# FLD_Logic.net
KiCad netlist of a schematic drawn in EAGLE
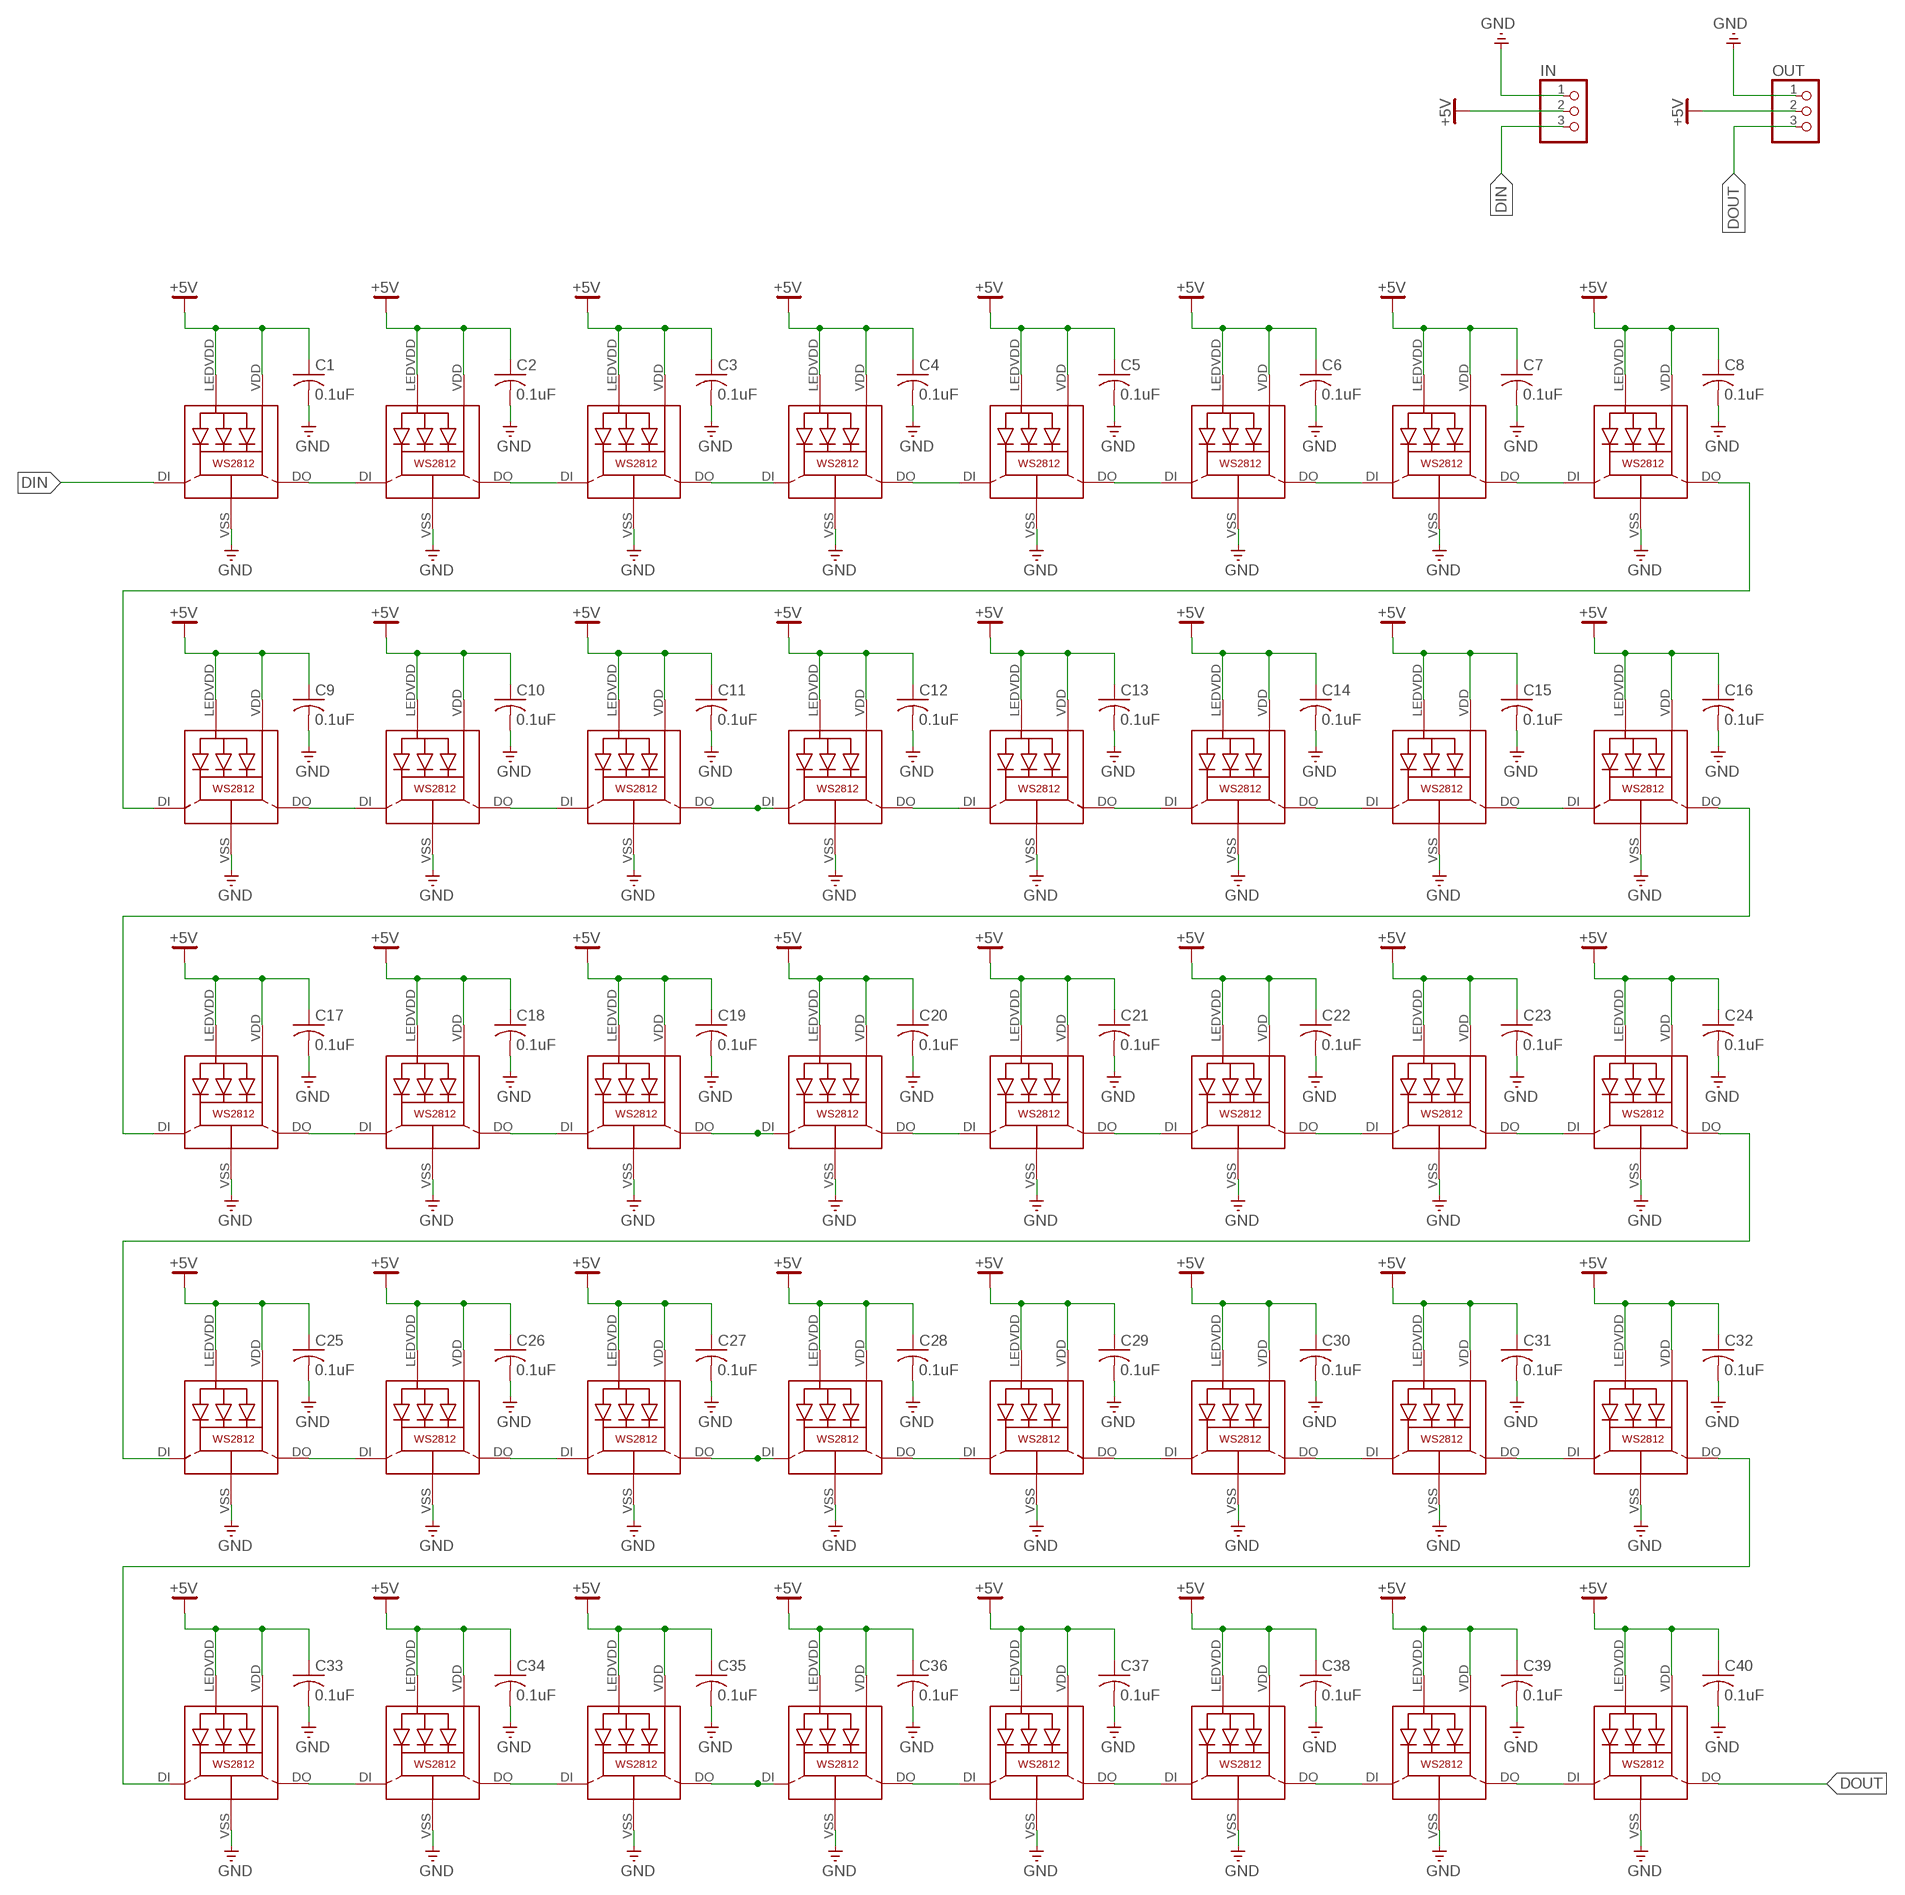
[diagram p0: schematic, sheet 1]

(export (version "E")
  (design (tool "Eeschema 10.0.6"))
  (components
    (comp (ref "C1")
      (value "0.1uF")
      (footprint "eagle-import:C0603")
      (libsource (lib "eagle-import") (part "C-USC0603"))
    )
    (comp (ref "C2")
      (value "0.1uF")
      (footprint "eagle-import:C0603")
      (libsource (lib "eagle-import") (part "C-USC0603"))
    )
    (comp (ref "C3")
      (value "0.1uF")
      (footprint "eagle-import:C0603")
      (libsource (lib "eagle-import") (part "C-USC0603"))
    )
    (comp (ref "C4")
      (value "0.1uF")
      (footprint "eagle-import:C0603")
      (libsource (lib "eagle-import") (part "C-USC0603"))
    )
    (comp (ref "C5")
      (value "0.1uF")
      (footprint "eagle-import:C0603")
      (libsource (lib "eagle-import") (part "C-USC0603"))
    )
    (comp (ref "C6")
      (value "0.1uF")
      (footprint "eagle-import:C0603")
      (libsource (lib "eagle-import") (part "C-USC0603"))
    )
    (comp (ref "C7")
      (value "0.1uF")
      (footprint "eagle-import:C0603")
      (libsource (lib "eagle-import") (part "C-USC0603"))
    )
    (comp (ref "C8")
      (value "0.1uF")
      (footprint "eagle-import:C0603")
      (libsource (lib "eagle-import") (part "C-USC0603"))
    )
    (comp (ref "C9")
      (value "0.1uF")
      (footprint "eagle-import:C0603")
      (libsource (lib "eagle-import") (part "C-USC0603"))
    )
    (comp (ref "C10")
      (value "0.1uF")
      (footprint "eagle-import:C0603")
      (libsource (lib "eagle-import") (part "C-USC0603"))
    )
    (comp (ref "C11")
      (value "0.1uF")
      (footprint "eagle-import:C0603")
      (libsource (lib "eagle-import") (part "C-USC0603"))
    )
    (comp (ref "C12")
      (value "0.1uF")
      (footprint "eagle-import:C0603")
      (libsource (lib "eagle-import") (part "C-USC0603"))
    )
    (comp (ref "C13")
      (value "0.1uF")
      (footprint "eagle-import:C0603")
      (libsource (lib "eagle-import") (part "C-USC0603"))
    )
    (comp (ref "C14")
      (value "0.1uF")
      (footprint "eagle-import:C0603")
      (libsource (lib "eagle-import") (part "C-USC0603"))
    )
    (comp (ref "C15")
      (value "0.1uF")
      (footprint "eagle-import:C0603")
      (libsource (lib "eagle-import") (part "C-USC0603"))
    )
    (comp (ref "C16")
      (value "0.1uF")
      (footprint "eagle-import:C0603")
      (libsource (lib "eagle-import") (part "C-USC0603"))
    )
    (comp (ref "C17")
      (value "0.1uF")
      (footprint "eagle-import:C0603")
      (libsource (lib "eagle-import") (part "C-USC0603"))
    )
    (comp (ref "C18")
      (value "0.1uF")
      (footprint "eagle-import:C0603")
      (libsource (lib "eagle-import") (part "C-USC0603"))
    )
    (comp (ref "C19")
      (value "0.1uF")
      (footprint "eagle-import:C0603")
      (libsource (lib "eagle-import") (part "C-USC0603"))
    )
    (comp (ref "C20")
      (value "0.1uF")
      (footprint "eagle-import:C0603")
      (libsource (lib "eagle-import") (part "C-USC0603"))
    )
    (comp (ref "C21")
      (value "0.1uF")
      (footprint "eagle-import:C0603")
      (libsource (lib "eagle-import") (part "C-USC0603"))
    )
    (comp (ref "C22")
      (value "0.1uF")
      (footprint "eagle-import:C0603")
      (libsource (lib "eagle-import") (part "C-USC0603"))
    )
    (comp (ref "C23")
      (value "0.1uF")
      (footprint "eagle-import:C0603")
      (libsource (lib "eagle-import") (part "C-USC0603"))
    )
    (comp (ref "C24")
      (value "0.1uF")
      (footprint "eagle-import:C0603")
      (libsource (lib "eagle-import") (part "C-USC0603"))
    )
    (comp (ref "C25")
      (value "0.1uF")
      (footprint "eagle-import:C0603")
      (libsource (lib "eagle-import") (part "C-USC0603"))
    )
    (comp (ref "C26")
      (value "0.1uF")
      (footprint "eagle-import:C0603")
      (libsource (lib "eagle-import") (part "C-USC0603"))
    )
    (comp (ref "C27")
      (value "0.1uF")
      (footprint "eagle-import:C0603")
      (libsource (lib "eagle-import") (part "C-USC0603"))
    )
    (comp (ref "C28")
      (value "0.1uF")
      (footprint "eagle-import:C0603")
      (libsource (lib "eagle-import") (part "C-USC0603"))
    )
    (comp (ref "C29")
      (value "0.1uF")
      (footprint "eagle-import:C0603")
      (libsource (lib "eagle-import") (part "C-USC0603"))
    )
    (comp (ref "C30")
      (value "0.1uF")
      (footprint "eagle-import:C0603")
      (libsource (lib "eagle-import") (part "C-USC0603"))
    )
    (comp (ref "C31")
      (value "0.1uF")
      (footprint "eagle-import:C0603")
      (libsource (lib "eagle-import") (part "C-USC0603"))
    )
    (comp (ref "C32")
      (value "0.1uF")
      (footprint "eagle-import:C0603")
      (libsource (lib "eagle-import") (part "C-USC0603"))
    )
    (comp (ref "C33")
      (value "0.1uF")
      (footprint "eagle-import:C0603")
      (libsource (lib "eagle-import") (part "C-USC0603"))
    )
    (comp (ref "C34")
      (value "0.1uF")
      (footprint "eagle-import:C0603")
      (libsource (lib "eagle-import") (part "C-USC0603"))
    )
    (comp (ref "C35")
      (value "0.1uF")
      (footprint "eagle-import:C0603")
      (libsource (lib "eagle-import") (part "C-USC0603"))
    )
    (comp (ref "C36")
      (value "0.1uF")
      (footprint "eagle-import:C0603")
      (libsource (lib "eagle-import") (part "C-USC0603"))
    )
    (comp (ref "C37")
      (value "0.1uF")
      (footprint "eagle-import:C0603")
      (libsource (lib "eagle-import") (part "C-USC0603"))
    )
    (comp (ref "C38")
      (value "0.1uF")
      (footprint "eagle-import:C0603")
      (libsource (lib "eagle-import") (part "C-USC0603"))
    )
    (comp (ref "C39")
      (value "0.1uF")
      (footprint "eagle-import:C0603")
      (libsource (lib "eagle-import") (part "C-USC0603"))
    )
    (comp (ref "C40")
      (value "0.1uF")
      (footprint "eagle-import:C0603")
      (libsource (lib "eagle-import") (part "C-USC0603"))
    )
    (comp (ref "IN")
      (value "PINHD-1X3")
      (footprint "eagle-import:1X03")
      (libsource (lib "eagle-import") (part "PINHD-1X3"))
    )
    (comp (ref "LED1")
      (value "WS2812")
      (footprint "eagle-import:WS2812")
      (libsource (lib "eagle-import") (part "WS2812"))
    )
    (comp (ref "LED2")
      (value "WS2812")
      (footprint "eagle-import:WS2812")
      (libsource (lib "eagle-import") (part "WS2812"))
    )
    (comp (ref "LED3")
      (value "WS2812")
      (footprint "eagle-import:WS2812")
      (libsource (lib "eagle-import") (part "WS2812"))
    )
    (comp (ref "LED4")
      (value "WS2812")
      (footprint "eagle-import:WS2812")
      (libsource (lib "eagle-import") (part "WS2812"))
    )
    (comp (ref "LED5")
      (value "WS2812")
      (footprint "eagle-import:WS2812")
      (libsource (lib "eagle-import") (part "WS2812"))
    )
    (comp (ref "LED6")
      (value "WS2812")
      (footprint "eagle-import:WS2812")
      (libsource (lib "eagle-import") (part "WS2812"))
    )
    (comp (ref "LED7")
      (value "WS2812")
      (footprint "eagle-import:WS2812")
      (libsource (lib "eagle-import") (part "WS2812"))
    )
    (comp (ref "LED8")
      (value "WS2812")
      (footprint "eagle-import:WS2812")
      (libsource (lib "eagle-import") (part "WS2812"))
    )
    (comp (ref "LED9")
      (value "WS2812")
      (footprint "eagle-import:WS2812")
      (libsource (lib "eagle-import") (part "WS2812"))
    )
    (comp (ref "LED10")
      (value "WS2812")
      (footprint "eagle-import:WS2812")
      (libsource (lib "eagle-import") (part "WS2812"))
    )
    (comp (ref "LED11")
      (value "WS2812")
      (footprint "eagle-import:WS2812")
      (libsource (lib "eagle-import") (part "WS2812"))
    )
    (comp (ref "LED12")
      (value "WS2812")
      (footprint "eagle-import:WS2812")
      (libsource (lib "eagle-import") (part "WS2812"))
    )
    (comp (ref "LED13")
      (value "WS2812")
      (footprint "eagle-import:WS2812")
      (libsource (lib "eagle-import") (part "WS2812"))
    )
    (comp (ref "LED14")
      (value "WS2812")
      (footprint "eagle-import:WS2812")
      (libsource (lib "eagle-import") (part "WS2812"))
    )
    (comp (ref "LED15")
      (value "WS2812")
      (footprint "eagle-import:WS2812")
      (libsource (lib "eagle-import") (part "WS2812"))
    )
    (comp (ref "LED16")
      (value "WS2812")
      (footprint "eagle-import:WS2812")
      (libsource (lib "eagle-import") (part "WS2812"))
    )
    (comp (ref "LED17")
      (value "WS2812")
      (footprint "eagle-import:WS2812")
      (libsource (lib "eagle-import") (part "WS2812"))
    )
    (comp (ref "LED18")
      (value "WS2812")
      (footprint "eagle-import:WS2812")
      (libsource (lib "eagle-import") (part "WS2812"))
    )
    (comp (ref "LED19")
      (value "WS2812")
      (footprint "eagle-import:WS2812")
      (libsource (lib "eagle-import") (part "WS2812"))
    )
    (comp (ref "LED20")
      (value "WS2812")
      (footprint "eagle-import:WS2812")
      (libsource (lib "eagle-import") (part "WS2812"))
    )
    (comp (ref "LED21")
      (value "WS2812")
      (footprint "eagle-import:WS2812")
      (libsource (lib "eagle-import") (part "WS2812"))
    )
    (comp (ref "LED22")
      (value "WS2812")
      (footprint "eagle-import:WS2812")
      (libsource (lib "eagle-import") (part "WS2812"))
    )
    (comp (ref "LED23")
      (value "WS2812")
      (footprint "eagle-import:WS2812")
      (libsource (lib "eagle-import") (part "WS2812"))
    )
    (comp (ref "LED24")
      (value "WS2812")
      (footprint "eagle-import:WS2812")
      (libsource (lib "eagle-import") (part "WS2812"))
    )
    (comp (ref "LED25")
      (value "WS2812")
      (footprint "eagle-import:WS2812")
      (libsource (lib "eagle-import") (part "WS2812"))
    )
    (comp (ref "LED26")
      (value "WS2812")
      (footprint "eagle-import:WS2812")
      (libsource (lib "eagle-import") (part "WS2812"))
    )
    (comp (ref "LED27")
      (value "WS2812")
      (footprint "eagle-import:WS2812")
      (libsource (lib "eagle-import") (part "WS2812"))
    )
    (comp (ref "LED28")
      (value "WS2812")
      (footprint "eagle-import:WS2812")
      (libsource (lib "eagle-import") (part "WS2812"))
    )
    (comp (ref "LED29")
      (value "WS2812")
      (footprint "eagle-import:WS2812")
      (libsource (lib "eagle-import") (part "WS2812"))
    )
    (comp (ref "LED30")
      (value "WS2812")
      (footprint "eagle-import:WS2812")
      (libsource (lib "eagle-import") (part "WS2812"))
    )
    (comp (ref "LED31")
      (value "WS2812")
      (footprint "eagle-import:WS2812")
      (libsource (lib "eagle-import") (part "WS2812"))
    )
    (comp (ref "LED32")
      (value "WS2812")
      (footprint "eagle-import:WS2812")
      (libsource (lib "eagle-import") (part "WS2812"))
    )
    (comp (ref "LED33")
      (value "WS2812")
      (footprint "eagle-import:WS2812")
      (libsource (lib "eagle-import") (part "WS2812"))
    )
    (comp (ref "LED34")
      (value "WS2812")
      (footprint "eagle-import:WS2812")
      (libsource (lib "eagle-import") (part "WS2812"))
    )
    (comp (ref "LED35")
      (value "WS2812")
      (footprint "eagle-import:WS2812")
      (libsource (lib "eagle-import") (part "WS2812"))
    )
    (comp (ref "LED36")
      (value "WS2812")
      (footprint "eagle-import:WS2812")
      (libsource (lib "eagle-import") (part "WS2812"))
    )
    (comp (ref "LED37")
      (value "WS2812")
      (footprint "eagle-import:WS2812")
      (libsource (lib "eagle-import") (part "WS2812"))
    )
    (comp (ref "LED38")
      (value "WS2812")
      (footprint "eagle-import:WS2812")
      (libsource (lib "eagle-import") (part "WS2812"))
    )
    (comp (ref "LED39")
      (value "WS2812")
      (footprint "eagle-import:WS2812")
      (libsource (lib "eagle-import") (part "WS2812"))
    )
    (comp (ref "LED40")
      (value "WS2812")
      (footprint "eagle-import:WS2812")
      (libsource (lib "eagle-import") (part "WS2812"))
    )
    (comp (ref "OUT")
      (value "PINHD-1X3")
      (footprint "eagle-import:1X03")
      (libsource (lib "eagle-import") (part "PINHD-1X3"))
    )
  )
  (nets
    (net (code "1") (name "+5V") (class "Default")
      (node (ref "C1") (pin "1") (pinfunction "1_1") (pintype "passive"))
      (node (ref "C10") (pin "1") (pinfunction "1_1") (pintype "passive"))
      (node (ref "C11") (pin "1") (pinfunction "1_1") (pintype "passive"))
      (node (ref "C12") (pin "1") (pinfunction "1_1") (pintype "passive"))
      (node (ref "C13") (pin "1") (pinfunction "1_1") (pintype "passive"))
      (node (ref "C14") (pin "1") (pinfunction "1_1") (pintype "passive"))
      (node (ref "C15") (pin "1") (pinfunction "1_1") (pintype "passive"))
      (node (ref "C16") (pin "1") (pinfunction "1_1") (pintype "passive"))
      (node (ref "C17") (pin "1") (pinfunction "1_1") (pintype "passive"))
      (node (ref "C18") (pin "1") (pinfunction "1_1") (pintype "passive"))
      (node (ref "C19") (pin "1") (pinfunction "1_1") (pintype "passive"))
      (node (ref "C2") (pin "1") (pinfunction "1_1") (pintype "passive"))
      (node (ref "C20") (pin "1") (pinfunction "1_1") (pintype "passive"))
      (node (ref "C21") (pin "1") (pinfunction "1_1") (pintype "passive"))
      (node (ref "C22") (pin "1") (pinfunction "1_1") (pintype "passive"))
      (node (ref "C23") (pin "1") (pinfunction "1_1") (pintype "passive"))
      (node (ref "C24") (pin "1") (pinfunction "1_1") (pintype "passive"))
      (node (ref "C25") (pin "1") (pinfunction "1_1") (pintype "passive"))
      (node (ref "C26") (pin "1") (pinfunction "1_1") (pintype "passive"))
      (node (ref "C27") (pin "1") (pinfunction "1_1") (pintype "passive"))
      (node (ref "C28") (pin "1") (pinfunction "1_1") (pintype "passive"))
      (node (ref "C29") (pin "1") (pinfunction "1_1") (pintype "passive"))
      (node (ref "C3") (pin "1") (pinfunction "1_1") (pintype "passive"))
      (node (ref "C30") (pin "1") (pinfunction "1_1") (pintype "passive"))
      (node (ref "C31") (pin "1") (pinfunction "1_1") (pintype "passive"))
      (node (ref "C32") (pin "1") (pinfunction "1_1") (pintype "passive"))
      (node (ref "C33") (pin "1") (pinfunction "1_1") (pintype "passive"))
      (node (ref "C34") (pin "1") (pinfunction "1_1") (pintype "passive"))
      (node (ref "C35") (pin "1") (pinfunction "1_1") (pintype "passive"))
      (node (ref "C36") (pin "1") (pinfunction "1_1") (pintype "passive"))
      (node (ref "C37") (pin "1") (pinfunction "1_1") (pintype "passive"))
      (node (ref "C38") (pin "1") (pinfunction "1_1") (pintype "passive"))
      (node (ref "C39") (pin "1") (pinfunction "1_1") (pintype "passive"))
      (node (ref "C4") (pin "1") (pinfunction "1_1") (pintype "passive"))
      (node (ref "C40") (pin "1") (pinfunction "1_1") (pintype "passive"))
      (node (ref "C5") (pin "1") (pinfunction "1_1") (pintype "passive"))
      (node (ref "C6") (pin "1") (pinfunction "1_1") (pintype "passive"))
      (node (ref "C7") (pin "1") (pinfunction "1_1") (pintype "passive"))
      (node (ref "C8") (pin "1") (pinfunction "1_1") (pintype "passive"))
      (node (ref "C9") (pin "1") (pinfunction "1_1") (pintype "passive"))
      (node (ref "IN") (pin "2") (pinfunction "2_2") (pintype "passive"))
      (node (ref "LED1") (pin "LEDVDD") (pinfunction "LEDVDD_LEDVDD") (pintype "power_in"))
      (node (ref "LED1") (pin "VDD") (pinfunction "VDD_VDD") (pintype "power_in"))
      (node (ref "LED10") (pin "LEDVDD") (pinfunction "LEDVDD_LEDVDD") (pintype "power_in"))
      (node (ref "LED10") (pin "VDD") (pinfunction "VDD_VDD") (pintype "power_in"))
      (node (ref "LED11") (pin "LEDVDD") (pinfunction "LEDVDD_LEDVDD") (pintype "power_in"))
      (node (ref "LED11") (pin "VDD") (pinfunction "VDD_VDD") (pintype "power_in"))
      (node (ref "LED12") (pin "LEDVDD") (pinfunction "LEDVDD_LEDVDD") (pintype "power_in"))
      (node (ref "LED12") (pin "VDD") (pinfunction "VDD_VDD") (pintype "power_in"))
      (node (ref "LED13") (pin "LEDVDD") (pinfunction "LEDVDD_LEDVDD") (pintype "power_in"))
      (node (ref "LED13") (pin "VDD") (pinfunction "VDD_VDD") (pintype "power_in"))
      (node (ref "LED14") (pin "LEDVDD") (pinfunction "LEDVDD_LEDVDD") (pintype "power_in"))
      (node (ref "LED14") (pin "VDD") (pinfunction "VDD_VDD") (pintype "power_in"))
      (node (ref "LED15") (pin "LEDVDD") (pinfunction "LEDVDD_LEDVDD") (pintype "power_in"))
      (node (ref "LED15") (pin "VDD") (pinfunction "VDD_VDD") (pintype "power_in"))
      (node (ref "LED16") (pin "LEDVDD") (pinfunction "LEDVDD_LEDVDD") (pintype "power_in"))
      (node (ref "LED16") (pin "VDD") (pinfunction "VDD_VDD") (pintype "power_in"))
      (node (ref "LED17") (pin "LEDVDD") (pinfunction "LEDVDD_LEDVDD") (pintype "power_in"))
      (node (ref "LED17") (pin "VDD") (pinfunction "VDD_VDD") (pintype "power_in"))
      (node (ref "LED18") (pin "LEDVDD") (pinfunction "LEDVDD_LEDVDD") (pintype "power_in"))
      (node (ref "LED18") (pin "VDD") (pinfunction "VDD_VDD") (pintype "power_in"))
      (node (ref "LED19") (pin "LEDVDD") (pinfunction "LEDVDD_LEDVDD") (pintype "power_in"))
      (node (ref "LED19") (pin "VDD") (pinfunction "VDD_VDD") (pintype "power_in"))
      (node (ref "LED2") (pin "LEDVDD") (pinfunction "LEDVDD_LEDVDD") (pintype "power_in"))
      (node (ref "LED2") (pin "VDD") (pinfunction "VDD_VDD") (pintype "power_in"))
      (node (ref "LED20") (pin "LEDVDD") (pinfunction "LEDVDD_LEDVDD") (pintype "power_in"))
      (node (ref "LED20") (pin "VDD") (pinfunction "VDD_VDD") (pintype "power_in"))
      (node (ref "LED21") (pin "LEDVDD") (pinfunction "LEDVDD_LEDVDD") (pintype "power_in"))
      (node (ref "LED21") (pin "VDD") (pinfunction "VDD_VDD") (pintype "power_in"))
      (node (ref "LED22") (pin "LEDVDD") (pinfunction "LEDVDD_LEDVDD") (pintype "power_in"))
      (node (ref "LED22") (pin "VDD") (pinfunction "VDD_VDD") (pintype "power_in"))
      (node (ref "LED23") (pin "LEDVDD") (pinfunction "LEDVDD_LEDVDD") (pintype "power_in"))
      (node (ref "LED23") (pin "VDD") (pinfunction "VDD_VDD") (pintype "power_in"))
      (node (ref "LED24") (pin "LEDVDD") (pinfunction "LEDVDD_LEDVDD") (pintype "power_in"))
      (node (ref "LED24") (pin "VDD") (pinfunction "VDD_VDD") (pintype "power_in"))
      (node (ref "LED25") (pin "LEDVDD") (pinfunction "LEDVDD_LEDVDD") (pintype "power_in"))
      (node (ref "LED25") (pin "VDD") (pinfunction "VDD_VDD") (pintype "power_in"))
      (node (ref "LED26") (pin "LEDVDD") (pinfunction "LEDVDD_LEDVDD") (pintype "power_in"))
      (node (ref "LED26") (pin "VDD") (pinfunction "VDD_VDD") (pintype "power_in"))
      (node (ref "LED27") (pin "LEDVDD") (pinfunction "LEDVDD_LEDVDD") (pintype "power_in"))
      (node (ref "LED27") (pin "VDD") (pinfunction "VDD_VDD") (pintype "power_in"))
      (node (ref "LED28") (pin "LEDVDD") (pinfunction "LEDVDD_LEDVDD") (pintype "power_in"))
      (node (ref "LED28") (pin "VDD") (pinfunction "VDD_VDD") (pintype "power_in"))
      (node (ref "LED29") (pin "LEDVDD") (pinfunction "LEDVDD_LEDVDD") (pintype "power_in"))
      (node (ref "LED29") (pin "VDD") (pinfunction "VDD_VDD") (pintype "power_in"))
      (node (ref "LED3") (pin "LEDVDD") (pinfunction "LEDVDD_LEDVDD") (pintype "power_in"))
      (node (ref "LED3") (pin "VDD") (pinfunction "VDD_VDD") (pintype "power_in"))
      (node (ref "LED30") (pin "LEDVDD") (pinfunction "LEDVDD_LEDVDD") (pintype "power_in"))
      (node (ref "LED30") (pin "VDD") (pinfunction "VDD_VDD") (pintype "power_in"))
      (node (ref "LED31") (pin "LEDVDD") (pinfunction "LEDVDD_LEDVDD") (pintype "power_in"))
      (node (ref "LED31") (pin "VDD") (pinfunction "VDD_VDD") (pintype "power_in"))
      (node (ref "LED32") (pin "LEDVDD") (pinfunction "LEDVDD_LEDVDD") (pintype "power_in"))
      (node (ref "LED32") (pin "VDD") (pinfunction "VDD_VDD") (pintype "power_in"))
      (node (ref "LED33") (pin "LEDVDD") (pinfunction "LEDVDD_LEDVDD") (pintype "power_in"))
      (node (ref "LED33") (pin "VDD") (pinfunction "VDD_VDD") (pintype "power_in"))
      (node (ref "LED34") (pin "LEDVDD") (pinfunction "LEDVDD_LEDVDD") (pintype "power_in"))
      (node (ref "LED34") (pin "VDD") (pinfunction "VDD_VDD") (pintype "power_in"))
      (node (ref "LED35") (pin "LEDVDD") (pinfunction "LEDVDD_LEDVDD") (pintype "power_in"))
      (node (ref "LED35") (pin "VDD") (pinfunction "VDD_VDD") (pintype "power_in"))
      (node (ref "LED36") (pin "LEDVDD") (pinfunction "LEDVDD_LEDVDD") (pintype "power_in"))
      (node (ref "LED36") (pin "VDD") (pinfunction "VDD_VDD") (pintype "power_in"))
      (node (ref "LED37") (pin "LEDVDD") (pinfunction "LEDVDD_LEDVDD") (pintype "power_in"))
      (node (ref "LED37") (pin "VDD") (pinfunction "VDD_VDD") (pintype "power_in"))
      (node (ref "LED38") (pin "LEDVDD") (pinfunction "LEDVDD_LEDVDD") (pintype "power_in"))
      (node (ref "LED38") (pin "VDD") (pinfunction "VDD_VDD") (pintype "power_in"))
      (node (ref "LED39") (pin "LEDVDD") (pinfunction "LEDVDD_LEDVDD") (pintype "power_in"))
      (node (ref "LED39") (pin "VDD") (pinfunction "VDD_VDD") (pintype "power_in"))
      (node (ref "LED4") (pin "LEDVDD") (pinfunction "LEDVDD_LEDVDD") (pintype "power_in"))
      (node (ref "LED4") (pin "VDD") (pinfunction "VDD_VDD") (pintype "power_in"))
      (node (ref "LED40") (pin "LEDVDD") (pinfunction "LEDVDD_LEDVDD") (pintype "power_in"))
      (node (ref "LED40") (pin "VDD") (pinfunction "VDD_VDD") (pintype "power_in"))
      (node (ref "LED5") (pin "LEDVDD") (pinfunction "LEDVDD_LEDVDD") (pintype "power_in"))
      (node (ref "LED5") (pin "VDD") (pinfunction "VDD_VDD") (pintype "power_in"))
      (node (ref "LED6") (pin "LEDVDD") (pinfunction "LEDVDD_LEDVDD") (pintype "power_in"))
      (node (ref "LED6") (pin "VDD") (pinfunction "VDD_VDD") (pintype "power_in"))
      (node (ref "LED7") (pin "LEDVDD") (pinfunction "LEDVDD_LEDVDD") (pintype "power_in"))
      (node (ref "LED7") (pin "VDD") (pinfunction "VDD_VDD") (pintype "power_in"))
      (node (ref "LED8") (pin "LEDVDD") (pinfunction "LEDVDD_LEDVDD") (pintype "power_in"))
      (node (ref "LED8") (pin "VDD") (pinfunction "VDD_VDD") (pintype "power_in"))
      (node (ref "LED9") (pin "LEDVDD") (pinfunction "LEDVDD_LEDVDD") (pintype "power_in"))
      (node (ref "LED9") (pin "VDD") (pinfunction "VDD_VDD") (pintype "power_in"))
      (node (ref "OUT") (pin "2") (pinfunction "2_2") (pintype "passive"))
    )
    (net (code "2") (name "DIN") (class "Default")
      (node (ref "IN") (pin "3") (pinfunction "3_3") (pintype "passive"))
      (node (ref "LED1") (pin "DI") (pinfunction "DI_DI") (pintype "input"))
    )
    (net (code "3") (name "DOUT") (class "Default")
      (node (ref "LED40") (pin "DO") (pinfunction "DO_DO") (pintype "output"))
      (node (ref "OUT") (pin "3") (pinfunction "3_3") (pintype "passive"))
    )
    (net (code "4") (name "GND") (class "Default")
      (node (ref "C1") (pin "2") (pinfunction "2_2") (pintype "passive"))
      (node (ref "C10") (pin "2") (pinfunction "2_2") (pintype "passive"))
      (node (ref "C11") (pin "2") (pinfunction "2_2") (pintype "passive"))
      (node (ref "C12") (pin "2") (pinfunction "2_2") (pintype "passive"))
      (node (ref "C13") (pin "2") (pinfunction "2_2") (pintype "passive"))
      (node (ref "C14") (pin "2") (pinfunction "2_2") (pintype "passive"))
      (node (ref "C15") (pin "2") (pinfunction "2_2") (pintype "passive"))
      (node (ref "C16") (pin "2") (pinfunction "2_2") (pintype "passive"))
      (node (ref "C17") (pin "2") (pinfunction "2_2") (pintype "passive"))
      (node (ref "C18") (pin "2") (pinfunction "2_2") (pintype "passive"))
      (node (ref "C19") (pin "2") (pinfunction "2_2") (pintype "passive"))
      (node (ref "C2") (pin "2") (pinfunction "2_2") (pintype "passive"))
      (node (ref "C20") (pin "2") (pinfunction "2_2") (pintype "passive"))
      (node (ref "C21") (pin "2") (pinfunction "2_2") (pintype "passive"))
      (node (ref "C22") (pin "2") (pinfunction "2_2") (pintype "passive"))
      (node (ref "C23") (pin "2") (pinfunction "2_2") (pintype "passive"))
      (node (ref "C24") (pin "2") (pinfunction "2_2") (pintype "passive"))
      (node (ref "C25") (pin "2") (pinfunction "2_2") (pintype "passive"))
      (node (ref "C26") (pin "2") (pinfunction "2_2") (pintype "passive"))
      (node (ref "C27") (pin "2") (pinfunction "2_2") (pintype "passive"))
      (node (ref "C28") (pin "2") (pinfunction "2_2") (pintype "passive"))
      (node (ref "C29") (pin "2") (pinfunction "2_2") (pintype "passive"))
      (node (ref "C3") (pin "2") (pinfunction "2_2") (pintype "passive"))
      (node (ref "C30") (pin "2") (pinfunction "2_2") (pintype "passive"))
      (node (ref "C31") (pin "2") (pinfunction "2_2") (pintype "passive"))
      (node (ref "C32") (pin "2") (pinfunction "2_2") (pintype "passive"))
      (node (ref "C33") (pin "2") (pinfunction "2_2") (pintype "passive"))
      (node (ref "C34") (pin "2") (pinfunction "2_2") (pintype "passive"))
      (node (ref "C35") (pin "2") (pinfunction "2_2") (pintype "passive"))
      (node (ref "C36") (pin "2") (pinfunction "2_2") (pintype "passive"))
      (node (ref "C37") (pin "2") (pinfunction "2_2") (pintype "passive"))
      (node (ref "C38") (pin "2") (pinfunction "2_2") (pintype "passive"))
      (node (ref "C39") (pin "2") (pinfunction "2_2") (pintype "passive"))
      (node (ref "C4") (pin "2") (pinfunction "2_2") (pintype "passive"))
      (node (ref "C40") (pin "2") (pinfunction "2_2") (pintype "passive"))
      (node (ref "C5") (pin "2") (pinfunction "2_2") (pintype "passive"))
      (node (ref "C6") (pin "2") (pinfunction "2_2") (pintype "passive"))
      (node (ref "C7") (pin "2") (pinfunction "2_2") (pintype "passive"))
      (node (ref "C8") (pin "2") (pinfunction "2_2") (pintype "passive"))
      (node (ref "C9") (pin "2") (pinfunction "2_2") (pintype "passive"))
      (node (ref "IN") (pin "1") (pinfunction "1_1") (pintype "passive"))
      (node (ref "LED1") (pin "VSS") (pinfunction "GND_VSS") (pintype "power_in"))
      (node (ref "LED10") (pin "VSS") (pinfunction "GND_VSS") (pintype "power_in"))
      (node (ref "LED11") (pin "VSS") (pinfunction "GND_VSS") (pintype "power_in"))
      (node (ref "LED12") (pin "VSS") (pinfunction "GND_VSS") (pintype "power_in"))
      (node (ref "LED13") (pin "VSS") (pinfunction "GND_VSS") (pintype "power_in"))
      (node (ref "LED14") (pin "VSS") (pinfunction "GND_VSS") (pintype "power_in"))
      (node (ref "LED15") (pin "VSS") (pinfunction "GND_VSS") (pintype "power_in"))
      (node (ref "LED16") (pin "VSS") (pinfunction "GND_VSS") (pintype "power_in"))
      (node (ref "LED17") (pin "VSS") (pinfunction "GND_VSS") (pintype "power_in"))
      (node (ref "LED18") (pin "VSS") (pinfunction "GND_VSS") (pintype "power_in"))
      (node (ref "LED19") (pin "VSS") (pinfunction "GND_VSS") (pintype "power_in"))
      (node (ref "LED2") (pin "VSS") (pinfunction "GND_VSS") (pintype "power_in"))
      (node (ref "LED20") (pin "VSS") (pinfunction "GND_VSS") (pintype "power_in"))
      (node (ref "LED21") (pin "VSS") (pinfunction "GND_VSS") (pintype "power_in"))
      (node (ref "LED22") (pin "VSS") (pinfunction "GND_VSS") (pintype "power_in"))
      (node (ref "LED23") (pin "VSS") (pinfunction "GND_VSS") (pintype "power_in"))
      (node (ref "LED24") (pin "VSS") (pinfunction "GND_VSS") (pintype "power_in"))
      (node (ref "LED25") (pin "VSS") (pinfunction "GND_VSS") (pintype "power_in"))
      (node (ref "LED26") (pin "VSS") (pinfunction "GND_VSS") (pintype "power_in"))
      (node (ref "LED27") (pin "VSS") (pinfunction "GND_VSS") (pintype "power_in"))
      (node (ref "LED28") (pin "VSS") (pinfunction "GND_VSS") (pintype "power_in"))
      (node (ref "LED29") (pin "VSS") (pinfunction "GND_VSS") (pintype "power_in"))
      (node (ref "LED3") (pin "VSS") (pinfunction "GND_VSS") (pintype "power_in"))
      (node (ref "LED30") (pin "VSS") (pinfunction "GND_VSS") (pintype "power_in"))
      (node (ref "LED31") (pin "VSS") (pinfunction "GND_VSS") (pintype "power_in"))
      (node (ref "LED32") (pin "VSS") (pinfunction "GND_VSS") (pintype "power_in"))
      (node (ref "LED33") (pin "VSS") (pinfunction "GND_VSS") (pintype "power_in"))
      (node (ref "LED34") (pin "VSS") (pinfunction "GND_VSS") (pintype "power_in"))
      (node (ref "LED35") (pin "VSS") (pinfunction "GND_VSS") (pintype "power_in"))
      (node (ref "LED36") (pin "VSS") (pinfunction "GND_VSS") (pintype "power_in"))
      (node (ref "LED37") (pin "VSS") (pinfunction "GND_VSS") (pintype "power_in"))
      (node (ref "LED38") (pin "VSS") (pinfunction "GND_VSS") (pintype "power_in"))
      (node (ref "LED39") (pin "VSS") (pinfunction "GND_VSS") (pintype "power_in"))
      (node (ref "LED4") (pin "VSS") (pinfunction "GND_VSS") (pintype "power_in"))
      (node (ref "LED40") (pin "VSS") (pinfunction "GND_VSS") (pintype "power_in"))
      (node (ref "LED5") (pin "VSS") (pinfunction "GND_VSS") (pintype "power_in"))
      (node (ref "LED6") (pin "VSS") (pinfunction "GND_VSS") (pintype "power_in"))
      (node (ref "LED7") (pin "VSS") (pinfunction "GND_VSS") (pintype "power_in"))
      (node (ref "LED8") (pin "VSS") (pinfunction "GND_VSS") (pintype "power_in"))
      (node (ref "LED9") (pin "VSS") (pinfunction "GND_VSS") (pintype "power_in"))
      (node (ref "OUT") (pin "1") (pinfunction "1_1") (pintype "passive"))
    )
    (net (code "5") (name "Net-(LED1-PadDO)") (class "Default")
      (node (ref "LED1") (pin "DO") (pinfunction "DO_DO") (pintype "output"))
      (node (ref "LED2") (pin "DI") (pinfunction "DI_DI") (pintype "input"))
    )
    (net (code "6") (name "Net-(LED2-PadDO)") (class "Default")
      (node (ref "LED2") (pin "DO") (pinfunction "DO_DO") (pintype "output"))
      (node (ref "LED3") (pin "DI") (pinfunction "DI_DI") (pintype "input"))
    )
    (net (code "7") (name "Net-(LED4-PadDO)") (class "Default")
      (node (ref "LED4") (pin "DO") (pinfunction "DO_DO") (pintype "output"))
      (node (ref "LED5") (pin "DI") (pinfunction "DI_DI") (pintype "input"))
    )
    (net (code "8") (name "Net-(LED5-PadDO)") (class "Default")
      (node (ref "LED5") (pin "DO") (pinfunction "DO_DO") (pintype "output"))
      (node (ref "LED6") (pin "DI") (pinfunction "DI_DI") (pintype "input"))
    )
    (net (code "9") (name "Net-(LED6-PadDO)") (class "Default")
      (node (ref "LED6") (pin "DO") (pinfunction "DO_DO") (pintype "output"))
      (node (ref "LED7") (pin "DI") (pinfunction "DI_DI") (pintype "input"))
    )
    (net (code "10") (name "Net-(LED7-PadDO)") (class "Default")
      (node (ref "LED7") (pin "DO") (pinfunction "DO_DO") (pintype "output"))
      (node (ref "LED8") (pin "DI") (pinfunction "DI_DI") (pintype "input"))
    )
    (net (code "11") (name "Net-(LED8-PadDO)") (class "Default")
      (node (ref "LED8") (pin "DO") (pinfunction "DO_DO") (pintype "output"))
      (node (ref "LED9") (pin "DI") (pinfunction "DI_DI") (pintype "input"))
    )
    (net (code "12") (name "Net-(LED10-PadDI)") (class "Default")
      (node (ref "LED10") (pin "DI") (pinfunction "DI_DI") (pintype "input"))
      (node (ref "LED9") (pin "DO") (pinfunction "DO_DO") (pintype "output"))
    )
    (net (code "13") (name "Net-(LED10-PadDO)") (class "Default")
      (node (ref "LED10") (pin "DO") (pinfunction "DO_DO") (pintype "output"))
      (node (ref "LED11") (pin "DI") (pinfunction "DI_DI") (pintype "input"))
    )
    (net (code "14") (name "Net-(LED11-PadDO)") (class "Default")
      (node (ref "LED11") (pin "DO") (pinfunction "DO_DO") (pintype "output"))
      (node (ref "LED12") (pin "DI") (pinfunction "DI_DI") (pintype "input"))
    )
    (net (code "15") (name "Net-(LED12-PadDO)") (class "Default")
      (node (ref "LED12") (pin "DO") (pinfunction "DO_DO") (pintype "output"))
      (node (ref "LED13") (pin "DI") (pinfunction "DI_DI") (pintype "input"))
    )
    (net (code "16") (name "Net-(LED13-PadDO)") (class "Default")
      (node (ref "LED13") (pin "DO") (pinfunction "DO_DO") (pintype "output"))
      (node (ref "LED14") (pin "DI") (pinfunction "DI_DI") (pintype "input"))
    )
    (net (code "17") (name "Net-(LED14-PadDO)") (class "Default")
      (node (ref "LED14") (pin "DO") (pinfunction "DO_DO") (pintype "output"))
      (node (ref "LED15") (pin "DI") (pinfunction "DI_DI") (pintype "input"))
    )
    (net (code "18") (name "Net-(LED15-PadDO)") (class "Default")
      (node (ref "LED15") (pin "DO") (pinfunction "DO_DO") (pintype "output"))
      (node (ref "LED16") (pin "DI") (pinfunction "DI_DI") (pintype "input"))
    )
    (net (code "19") (name "Net-(LED16-PadDO)") (class "Default")
      (node (ref "LED16") (pin "DO") (pinfunction "DO_DO") (pintype "output"))
      (node (ref "LED17") (pin "DI") (pinfunction "DI_DI") (pintype "input"))
    )
    (net (code "20") (name "Net-(LED17-PadDO)") (class "Default")
      (node (ref "LED17") (pin "DO") (pinfunction "DO_DO") (pintype "output"))
      (node (ref "LED18") (pin "DI") (pinfunction "DI_DI") (pintype "input"))
    )
    (net (code "21") (name "Net-(LED18-PadDO)") (class "Default")
      (node (ref "LED18") (pin "DO") (pinfunction "DO_DO") (pintype "output"))
      (node (ref "LED19") (pin "DI") (pinfunction "DI_DI") (pintype "input"))
    )
    (net (code "22") (name "Net-(LED19-PadDO)") (class "Default")
      (node (ref "LED19") (pin "DO") (pinfunction "DO_DO") (pintype "output"))
      (node (ref "LED20") (pin "DI") (pinfunction "DI_DI") (pintype "input"))
    )
    (net (code "23") (name "Net-(LED20-PadDO)") (class "Default")
      (node (ref "LED20") (pin "DO") (pinfunction "DO_DO") (pintype "output"))
      (node (ref "LED21") (pin "DI") (pinfunction "DI_DI") (pintype "input"))
    )
    (net (code "24") (name "Net-(LED21-PadDO)") (class "Default")
      (node (ref "LED21") (pin "DO") (pinfunction "DO_DO") (pintype "output"))
      (node (ref "LED22") (pin "DI") (pinfunction "DI_DI") (pintype "input"))
    )
    (net (code "25") (name "Net-(LED22-PadDO)") (class "Default")
      (node (ref "LED22") (pin "DO") (pinfunction "DO_DO") (pintype "output"))
      (node (ref "LED23") (pin "DI") (pinfunction "DI_DI") (pintype "input"))
    )
    (net (code "26") (name "Net-(LED23-PadDO)") (class "Default")
      (node (ref "LED23") (pin "DO") (pinfunction "DO_DO") (pintype "output"))
      (node (ref "LED24") (pin "DI") (pinfunction "DI_DI") (pintype "input"))
    )
    (net (code "27") (name "Net-(LED25-PadDO)") (class "Default")
      (node (ref "LED25") (pin "DO") (pinfunction "DO_DO") (pintype "output"))
      (node (ref "LED26") (pin "DI") (pinfunction "DI_DI") (pintype "input"))
    )
    (net (code "28") (name "Net-(LED26-PadDO)") (class "Default")
      (node (ref "LED26") (pin "DO") (pinfunction "DO_DO") (pintype "output"))
      (node (ref "LED27") (pin "DI") (pinfunction "DI_DI") (pintype "input"))
    )
    (net (code "29") (name "Net-(LED27-PadDO)") (class "Default")
      (node (ref "LED27") (pin "DO") (pinfunction "DO_DO") (pintype "output"))
      (node (ref "LED28") (pin "DI") (pinfunction "DI_DI") (pintype "input"))
    )
    (net (code "30") (name "Net-(LED28-PadDO)") (class "Default")
      (node (ref "LED28") (pin "DO") (pinfunction "DO_DO") (pintype "output"))
      (node (ref "LED29") (pin "DI") (pinfunction "DI_DI") (pintype "input"))
    )
    (net (code "31") (name "Net-(LED29-PadDO)") (class "Default")
      (node (ref "LED29") (pin "DO") (pinfunction "DO_DO") (pintype "output"))
      (node (ref "LED30") (pin "DI") (pinfunction "DI_DI") (pintype "input"))
    )
    (net (code "32") (name "Net-(LED30-PadDO)") (class "Default")
      (node (ref "LED30") (pin "DO") (pinfunction "DO_DO") (pintype "output"))
      (node (ref "LED31") (pin "DI") (pinfunction "DI_DI") (pintype "input"))
    )
    (net (code "33") (name "Net-(LED31-PadDO)") (class "Default")
      (node (ref "LED31") (pin "DO") (pinfunction "DO_DO") (pintype "output"))
      (node (ref "LED32") (pin "DI") (pinfunction "DI_DI") (pintype "input"))
    )
    (net (code "34") (name "Net-(LED33-PadDO)") (class "Default")
      (node (ref "LED33") (pin "DO") (pinfunction "DO_DO") (pintype "output"))
      (node (ref "LED34") (pin "DI") (pinfunction "DI_DI") (pintype "input"))
    )
    (net (code "35") (name "Net-(LED34-PadDO)") (class "Default")
      (node (ref "LED34") (pin "DO") (pinfunction "DO_DO") (pintype "output"))
      (node (ref "LED35") (pin "DI") (pinfunction "DI_DI") (pintype "input"))
    )
    (net (code "36") (name "Net-(LED35-PadDO)") (class "Default")
      (node (ref "LED35") (pin "DO") (pinfunction "DO_DO") (pintype "output"))
      (node (ref "LED36") (pin "DI") (pinfunction "DI_DI") (pintype "input"))
    )
    (net (code "37") (name "Net-(LED36-PadDO)") (class "Default")
      (node (ref "LED36") (pin "DO") (pinfunction "DO_DO") (pintype "output"))
      (node (ref "LED37") (pin "DI") (pinfunction "DI_DI") (pintype "input"))
    )
    (net (code "38") (name "Net-(LED37-PadDO)") (class "Default")
      (node (ref "LED37") (pin "DO") (pinfunction "DO_DO") (pintype "output"))
      (node (ref "LED38") (pin "DI") (pinfunction "DI_DI") (pintype "input"))
    )
    (net (code "39") (name "Net-(LED38-PadDO)") (class "Default")
      (node (ref "LED38") (pin "DO") (pinfunction "DO_DO") (pintype "output"))
      (node (ref "LED39") (pin "DI") (pinfunction "DI_DI") (pintype "input"))
    )
    (net (code "40") (name "Net-(LED39-PadDO)") (class "Default")
      (node (ref "LED39") (pin "DO") (pinfunction "DO_DO") (pintype "output"))
      (node (ref "LED40") (pin "DI") (pinfunction "DI_DI") (pintype "input"))
    )
    (net (code "41") (name "unconnected-(LED3-PadDO)") (class "Default")
      (node (ref "LED3") (pin "DO") (pinfunction "DO_DO") (pintype "output"))
    )
    (net (code "42") (name "unconnected-(LED4-PadDI)") (class "Default")
      (node (ref "LED4") (pin "DI") (pinfunction "DI_DI") (pintype "input"))
    )
    (net (code "43") (name "unconnected-(LED24-PadDO)") (class "Default")
      (node (ref "LED24") (pin "DO") (pinfunction "DO_DO") (pintype "output"))
    )
    (net (code "44") (name "unconnected-(LED25-PadDI)") (class "Default")
      (node (ref "LED25") (pin "DI") (pinfunction "DI_DI") (pintype "input"))
    )
    (net (code "45") (name "unconnected-(LED32-PadDO)") (class "Default")
      (node (ref "LED32") (pin "DO") (pinfunction "DO_DO") (pintype "output"))
    )
    (net (code "46") (name "unconnected-(LED33-PadDI)") (class "Default")
      (node (ref "LED33") (pin "DI") (pinfunction "DI_DI") (pintype "input"))
    )
  )
)
